# EPM7064S.net
KiCad netlist of a schematic drawn in EAGLE
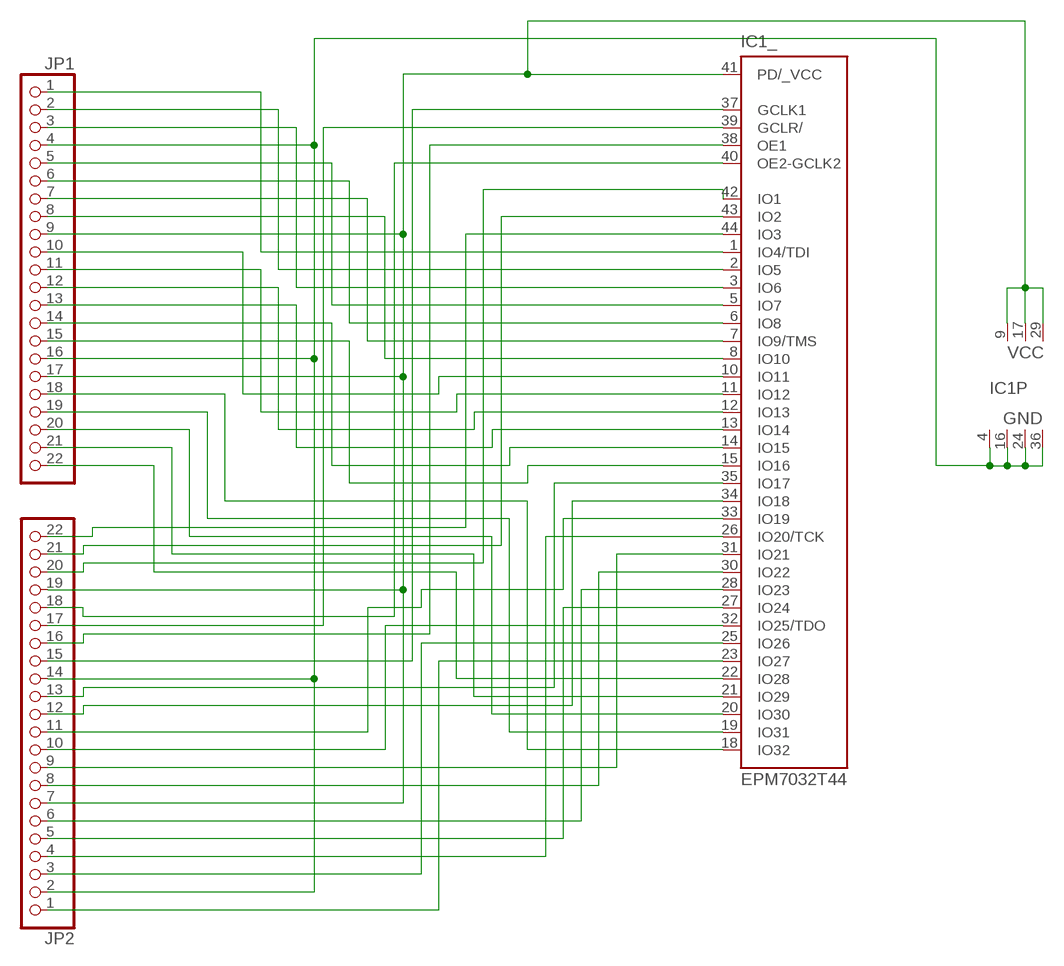
[diagram p0: schematic, sheet 1]

(export (version "E")
  (design (tool "Eeschema 10.0.6"))
  (components
    (comp (ref "IC1")
      (value "EPM7032T44")
      (footprint "eagle-import:TQFP44")
      (fields (field (name "MPN") "EPM7032SLC44-6N"))
      (libsource (lib "eagle-import") (part "EPM7032T44"))
    )
    (comp (ref "JP1")
      (value "PINHD-1X22")
      (footprint "eagle-import:1X22")
      (libsource (lib "eagle-import") (part "PINHD-1X22"))
    )
    (comp (ref "JP2")
      (value "PINHD-1X22")
      (footprint "eagle-import:1X22")
      (libsource (lib "eagle-import") (part "PINHD-1X22"))
    )
  )
  (nets
    (net (code "1") (name "Net-(IC1A-GND-Pad16)") (class "Default")
      (node (ref "IC1") (pin "16") (pinfunction "GND_16") (pintype "power_in"))
      (node (ref "IC1") (pin "24") (pinfunction "GND_24") (pintype "power_in"))
      (node (ref "IC1") (pin "36") (pinfunction "GND_36") (pintype "power_in"))
      (node (ref "IC1") (pin "4") (pinfunction "GND_4") (pintype "power_in"))
      (node (ref "JP1") (pin "16") (pinfunction "16_16") (pintype "passive"))
      (node (ref "JP1") (pin "4") (pinfunction "4_4") (pintype "passive"))
      (node (ref "JP2") (pin "14") (pinfunction "14_14") (pintype "passive"))
      (node (ref "JP2") (pin "2") (pinfunction "2_2") (pintype "passive"))
    )
    (net (code "2") (name "Net-(IC1B-GCLK1)") (class "Default")
      (node (ref "IC1") (pin "37") (pinfunction "GCLK1_37") (pintype "input"))
      (node (ref "JP2") (pin "15") (pinfunction "15_15") (pintype "passive"))
    )
    (net (code "3") (name "Net-(IC1B-GCLR{slash})") (class "Default")
      (node (ref "IC1") (pin "39") (pinfunction "GCLR/_39") (pintype "input"))
      (node (ref "JP2") (pin "17") (pinfunction "17_17") (pintype "passive"))
    )
    (net (code "4") (name "Net-(IC1B-IO1)") (class "Default")
      (node (ref "IC1") (pin "42") (pinfunction "IO1_42") (pintype "bidirectional"))
      (node (ref "JP2") (pin "20") (pinfunction "20_20") (pintype "passive"))
    )
    (net (code "5") (name "Net-(IC1B-IO2)") (class "Default")
      (node (ref "IC1") (pin "43") (pinfunction "IO2_43") (pintype "bidirectional"))
      (node (ref "JP2") (pin "21") (pinfunction "21_21") (pintype "passive"))
    )
    (net (code "6") (name "Net-(IC1B-IO3)") (class "Default")
      (node (ref "IC1") (pin "44") (pinfunction "IO3_44") (pintype "bidirectional"))
      (node (ref "JP2") (pin "22") (pinfunction "22_22") (pintype "passive"))
    )
    (net (code "7") (name "Net-(IC1B-IO4{slash}TDI)") (class "Default")
      (node (ref "IC1") (pin "1") (pinfunction "IO4/TDI_1") (pintype "bidirectional"))
      (node (ref "JP1") (pin "1") (pinfunction "1_1") (pintype "passive"))
    )
    (net (code "8") (name "Net-(IC1B-IO5)") (class "Default")
      (node (ref "IC1") (pin "2") (pinfunction "IO5_2") (pintype "bidirectional"))
      (node (ref "JP1") (pin "2") (pinfunction "2_2") (pintype "passive"))
    )
    (net (code "9") (name "Net-(IC1B-IO6)") (class "Default")
      (node (ref "IC1") (pin "3") (pinfunction "IO6_3") (pintype "bidirectional"))
      (node (ref "JP1") (pin "3") (pinfunction "3_3") (pintype "passive"))
    )
    (net (code "10") (name "Net-(IC1B-IO7)") (class "Default")
      (node (ref "IC1") (pin "5") (pinfunction "IO7_5") (pintype "bidirectional"))
      (node (ref "JP1") (pin "5") (pinfunction "5_5") (pintype "passive"))
    )
    (net (code "11") (name "Net-(IC1B-IO8)") (class "Default")
      (node (ref "IC1") (pin "6") (pinfunction "IO8_6") (pintype "bidirectional"))
      (node (ref "JP1") (pin "6") (pinfunction "6_6") (pintype "passive"))
    )
    (net (code "12") (name "Net-(IC1B-IO9{slash}TMS)") (class "Default")
      (node (ref "IC1") (pin "7") (pinfunction "IO9/TMS_7") (pintype "bidirectional"))
      (node (ref "JP1") (pin "7") (pinfunction "7_7") (pintype "passive"))
    )
    (net (code "13") (name "Net-(IC1B-IO10)") (class "Default")
      (node (ref "IC1") (pin "8") (pinfunction "IO10_8") (pintype "bidirectional"))
      (node (ref "JP1") (pin "8") (pinfunction "8_8") (pintype "passive"))
    )
    (net (code "14") (name "Net-(IC1B-IO11)") (class "Default")
      (node (ref "IC1") (pin "10") (pinfunction "IO11_10") (pintype "bidirectional"))
      (node (ref "JP1") (pin "10") (pinfunction "10_10") (pintype "passive"))
    )
    (net (code "15") (name "Net-(IC1B-IO12)") (class "Default")
      (node (ref "IC1") (pin "11") (pinfunction "IO12_11") (pintype "bidirectional"))
      (node (ref "JP1") (pin "11") (pinfunction "11_11") (pintype "passive"))
    )
    (net (code "16") (name "Net-(IC1B-IO13)") (class "Default")
      (node (ref "IC1") (pin "12") (pinfunction "IO13_12") (pintype "bidirectional"))
      (node (ref "JP1") (pin "12") (pinfunction "12_12") (pintype "passive"))
    )
    (net (code "17") (name "Net-(IC1B-IO14)") (class "Default")
      (node (ref "IC1") (pin "13") (pinfunction "IO14_13") (pintype "bidirectional"))
      (node (ref "JP1") (pin "13") (pinfunction "13_13") (pintype "passive"))
    )
    (net (code "18") (name "Net-(IC1B-IO15)") (class "Default")
      (node (ref "IC1") (pin "14") (pinfunction "IO15_14") (pintype "bidirectional"))
      (node (ref "JP1") (pin "14") (pinfunction "14_14") (pintype "passive"))
    )
    (net (code "19") (name "Net-(IC1B-IO16)") (class "Default")
      (node (ref "IC1") (pin "15") (pinfunction "IO16_15") (pintype "bidirectional"))
      (node (ref "JP1") (pin "15") (pinfunction "15_15") (pintype "passive"))
    )
    (net (code "20") (name "Net-(IC1B-IO17)") (class "Default")
      (node (ref "IC1") (pin "35") (pinfunction "IO17_35") (pintype "bidirectional"))
      (node (ref "JP2") (pin "13") (pinfunction "13_13") (pintype "passive"))
    )
    (net (code "21") (name "Net-(IC1B-IO18)") (class "Default")
      (node (ref "IC1") (pin "34") (pinfunction "IO18_34") (pintype "bidirectional"))
      (node (ref "JP2") (pin "12") (pinfunction "12_12") (pintype "passive"))
    )
    (net (code "22") (name "Net-(IC1B-IO19)") (class "Default")
      (node (ref "IC1") (pin "33") (pinfunction "IO19_33") (pintype "bidirectional"))
      (node (ref "JP2") (pin "11") (pinfunction "11_11") (pintype "passive"))
    )
    (net (code "23") (name "Net-(IC1B-IO20{slash}TCK)") (class "Default")
      (node (ref "IC1") (pin "26") (pinfunction "IO20/TCK_26") (pintype "bidirectional"))
      (node (ref "JP2") (pin "4") (pinfunction "4_4") (pintype "passive"))
    )
    (net (code "24") (name "Net-(IC1B-IO21)") (class "Default")
      (node (ref "IC1") (pin "31") (pinfunction "IO21_31") (pintype "bidirectional"))
      (node (ref "JP2") (pin "9") (pinfunction "9_9") (pintype "passive"))
    )
    (net (code "25") (name "Net-(IC1B-IO22)") (class "Default")
      (node (ref "IC1") (pin "30") (pinfunction "IO22_30") (pintype "bidirectional"))
      (node (ref "JP2") (pin "8") (pinfunction "8_8") (pintype "passive"))
    )
    (net (code "26") (name "Net-(IC1B-IO23)") (class "Default")
      (node (ref "IC1") (pin "28") (pinfunction "IO23_28") (pintype "bidirectional"))
      (node (ref "JP2") (pin "6") (pinfunction "6_6") (pintype "passive"))
    )
    (net (code "27") (name "Net-(IC1B-IO24)") (class "Default")
      (node (ref "IC1") (pin "27") (pinfunction "IO24_27") (pintype "bidirectional"))
      (node (ref "JP2") (pin "5") (pinfunction "5_5") (pintype "passive"))
    )
    (net (code "28") (name "Net-(IC1B-IO25{slash}TDO)") (class "Default")
      (node (ref "IC1") (pin "32") (pinfunction "IO25/TDO_32") (pintype "bidirectional"))
      (node (ref "JP2") (pin "10") (pinfunction "10_10") (pintype "passive"))
    )
    (net (code "29") (name "Net-(IC1B-IO26)") (class "Default")
      (node (ref "IC1") (pin "25") (pinfunction "IO26_25") (pintype "bidirectional"))
      (node (ref "JP2") (pin "3") (pinfunction "3_3") (pintype "passive"))
    )
    (net (code "30") (name "Net-(IC1B-IO27)") (class "Default")
      (node (ref "IC1") (pin "23") (pinfunction "IO27_23") (pintype "bidirectional"))
      (node (ref "JP2") (pin "1") (pinfunction "1_1") (pintype "passive"))
    )
    (net (code "31") (name "Net-(IC1B-IO28)") (class "Default")
      (node (ref "IC1") (pin "22") (pinfunction "IO28_22") (pintype "bidirectional"))
      (node (ref "JP1") (pin "22") (pinfunction "22_22") (pintype "passive"))
    )
    (net (code "32") (name "Net-(IC1B-IO29)") (class "Default")
      (node (ref "IC1") (pin "21") (pinfunction "IO29_21") (pintype "bidirectional"))
      (node (ref "JP1") (pin "21") (pinfunction "21_21") (pintype "passive"))
    )
    (net (code "33") (name "Net-(IC1B-IO30)") (class "Default")
      (node (ref "IC1") (pin "20") (pinfunction "IO30_20") (pintype "bidirectional"))
      (node (ref "JP1") (pin "20") (pinfunction "20_20") (pintype "passive"))
    )
    (net (code "34") (name "Net-(IC1B-IO31)") (class "Default")
      (node (ref "IC1") (pin "19") (pinfunction "IO31_19") (pintype "bidirectional"))
      (node (ref "JP1") (pin "19") (pinfunction "19_19") (pintype "passive"))
    )
    (net (code "35") (name "Net-(IC1B-IO32)") (class "Default")
      (node (ref "IC1") (pin "18") (pinfunction "IO32_18") (pintype "bidirectional"))
      (node (ref "JP1") (pin "18") (pinfunction "18_18") (pintype "passive"))
    )
    (net (code "36") (name "Net-(IC1B-OE1)") (class "Default")
      (node (ref "IC1") (pin "38") (pinfunction "OE1_38") (pintype "input"))
      (node (ref "JP2") (pin "16") (pinfunction "16_16") (pintype "passive"))
    )
    (net (code "37") (name "Net-(IC1B-OE2-GCLK2)") (class "Default")
      (node (ref "IC1") (pin "40") (pinfunction "OE2-GCLK2_40") (pintype "input"))
      (node (ref "JP2") (pin "18") (pinfunction "18_18") (pintype "passive"))
    )
    (net (code "38") (name "Net-(IC1B-PD{slash}_VCC)") (class "Default")
      (node (ref "IC1") (pin "17") (pinfunction "VCC_17") (pintype "power_in"))
      (node (ref "IC1") (pin "29") (pinfunction "VCC_29") (pintype "power_in"))
      (node (ref "IC1") (pin "41") (pinfunction "PD/_VCC_41") (pintype "passive"))
      (node (ref "IC1") (pin "9") (pinfunction "VCC_9") (pintype "power_in"))
      (node (ref "JP1") (pin "17") (pinfunction "17_17") (pintype "passive"))
      (node (ref "JP1") (pin "9") (pinfunction "9_9") (pintype "passive"))
      (node (ref "JP2") (pin "19") (pinfunction "19_19") (pintype "passive"))
      (node (ref "JP2") (pin "7") (pinfunction "7_7") (pintype "passive"))
    )
  )
)
